# ESP8266_Relay.net
KiCad netlist of a schematic drawn in EAGLE
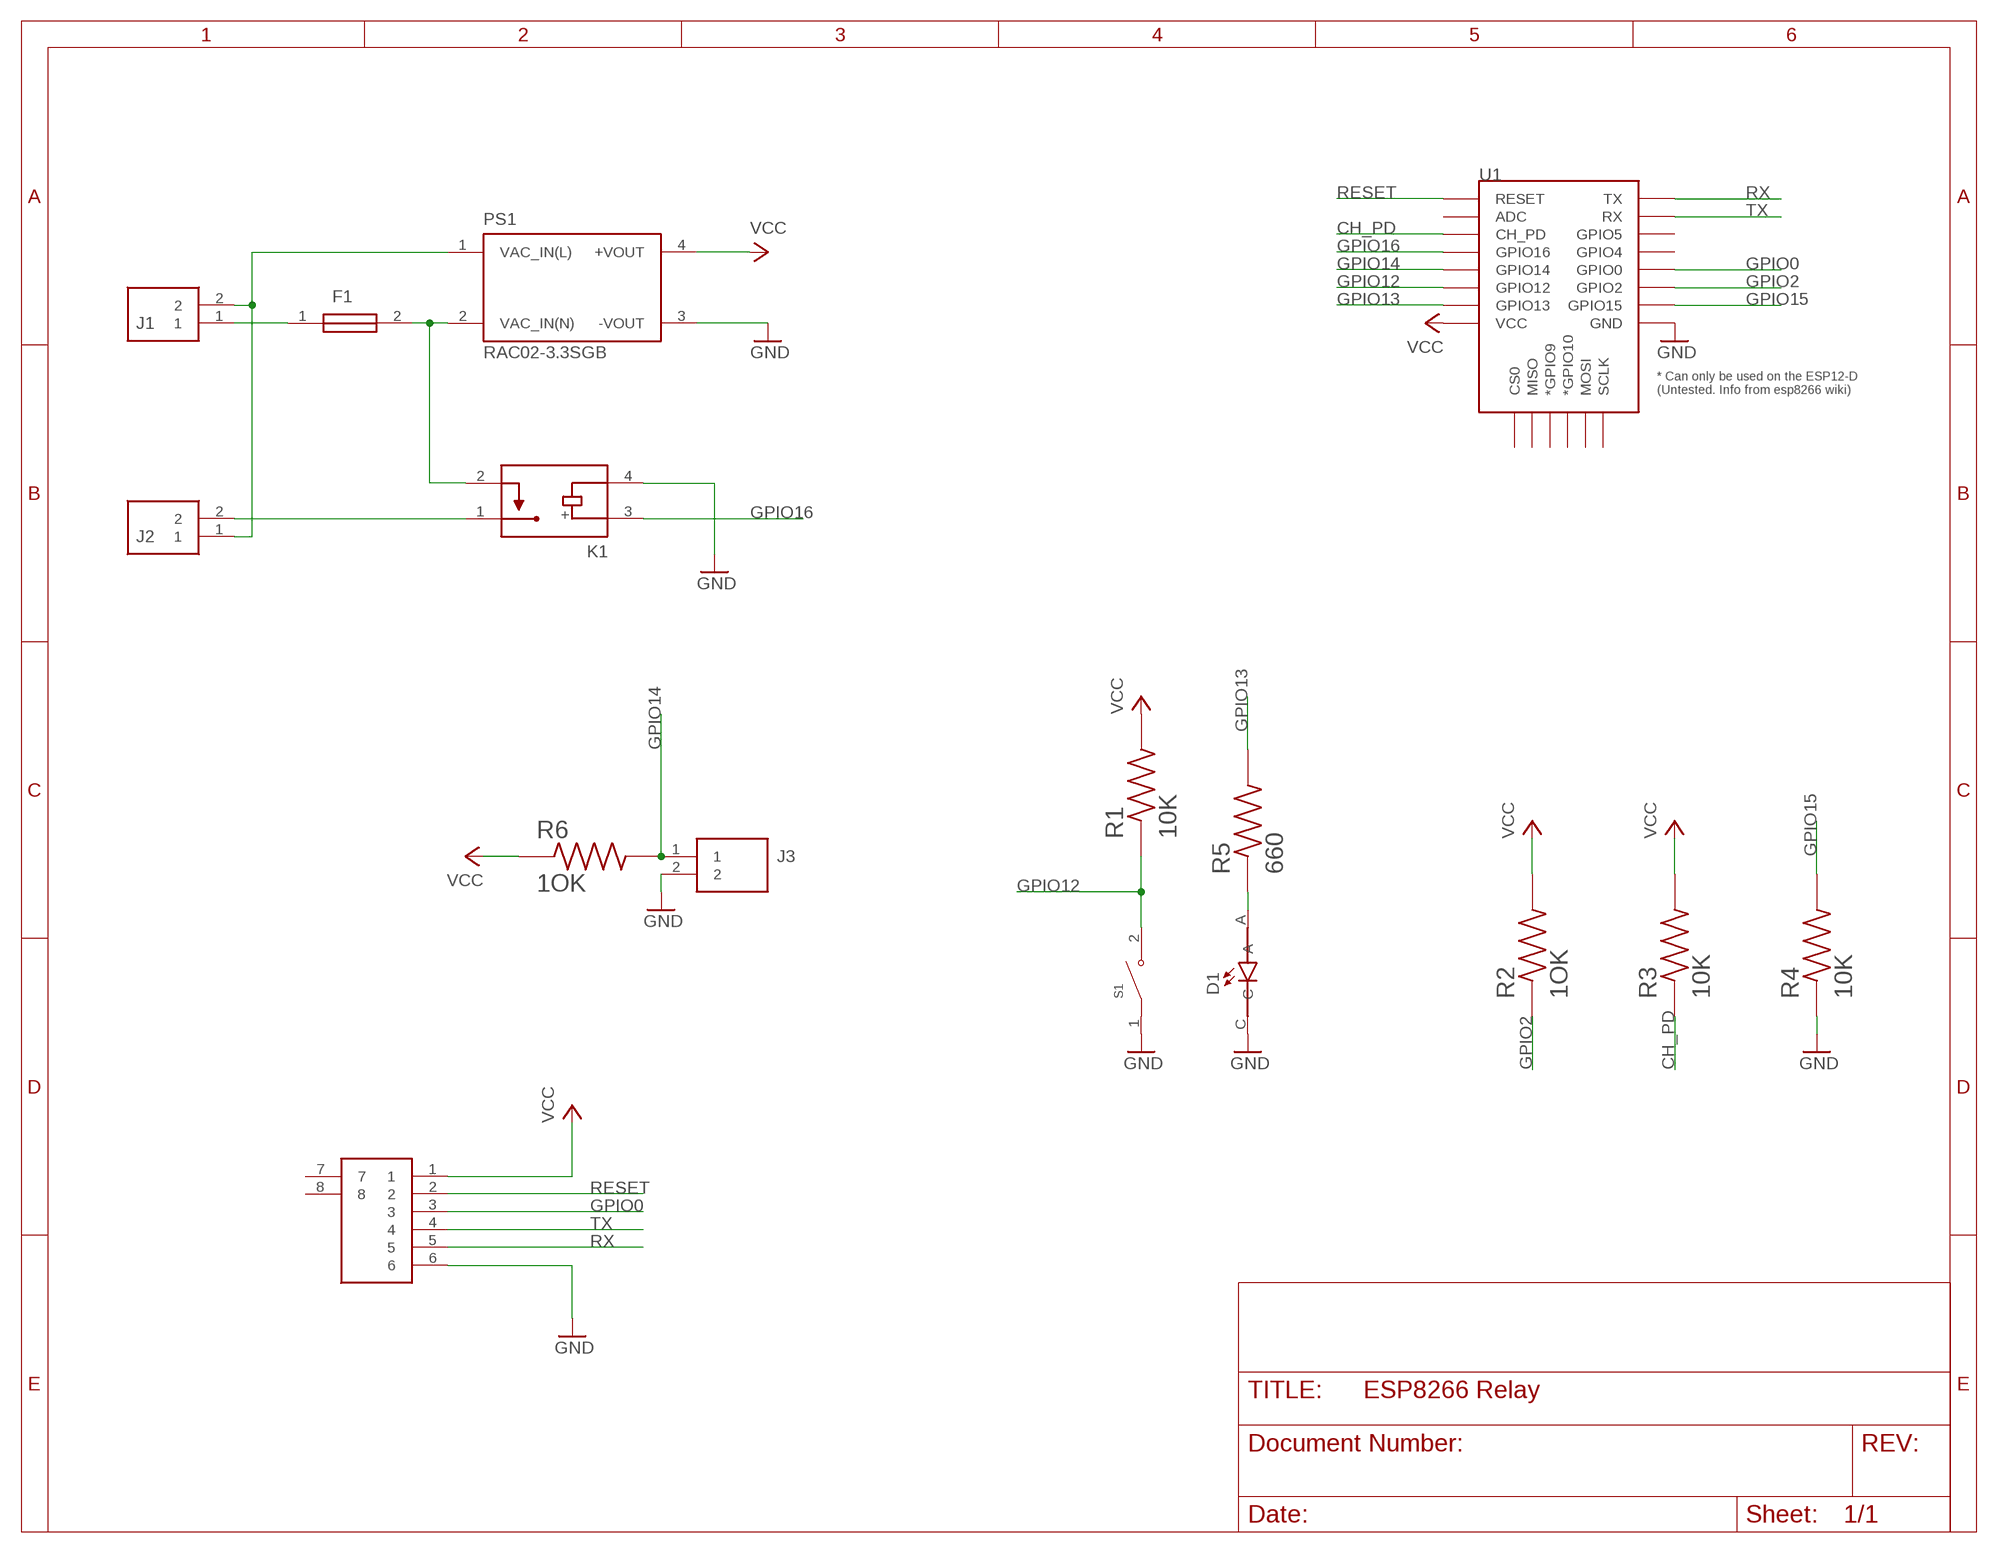
[diagram p0: schematic, sheet 1]

(export (version "E")
  (design (tool "Eeschema 10.0.6"))
  (components
    (comp (ref "D1")
      (value "SML-LXT0805IW-TR")
      (footprint "eagle-import:LEDC2012X120N")
      (fields (field (name "MF") "Lumex Opto/Components"))
      (libsource (lib "eagle-import") (part "SML-LXT0805IW-TR"))
    )
    (comp (ref "F1")
      (value "3404.2469.22")
      (footprint "eagle-import:3404246922")
      (fields (field (name "MOUSER_PART_NUMBER") "693-3404.2469.22"))
      (libsource (lib "eagle-import") (part "3404.2469.22"))
    )
    (comp (ref "J1")
      (value "TB006-508-02BE")
      (footprint "eagle-import:TB00650802BE")
      (fields (field (name "MOUSER_PART_NUMBER") "490-TB006-508-02BE"))
      (libsource (lib "eagle-import") (part "TB006-508-02BE"))
    )
    (comp (ref "J2")
      (value "TB006-508-02BE")
      (footprint "eagle-import:TB00650802BE")
      (fields (field (name "MOUSER_PART_NUMBER") "490-TB006-508-02BE"))
      (libsource (lib "eagle-import") (part "TB006-508-02BE"))
    )
    (comp (ref "J3")
      (value "TB006-508-02BE")
      (footprint "eagle-import:TB00650802BE")
      (fields (field (name "MOUSER_PART_NUMBER") "490-TB006-508-02BE"))
      (libsource (lib "eagle-import") (part "TB006-508-02BE"))
    )
    (comp (ref "J4")
      (value "52852-0670")
      (footprint "eagle-import:528520670")
      (fields (field (name "MOUSER_PART_NUMBER") "538-52852-0670"))
      (libsource (lib "eagle-import") (part "52852-0670"))
    )
    (comp (ref "K1")
      (value "G3MB-202PDC5")
      (footprint "eagle-import:RELAY_G3MB-202PDC5")
      (fields (field (name "MF") "Omron Automation") (field (name "MP") "G3MB-202P DC5"))
      (libsource (lib "eagle-import") (part "G3MB-202PDC5"))
    )
    (comp (ref "PS1")
      (value "RAC02-3.3SGB")
      (footprint "eagle-import:CONV_RAC02-3.3SGB")
      (fields (field (name "MF") "Recom Power"))
      (libsource (lib "eagle-import") (part "RAC02-3.3SGB"))
    )
    (comp (ref "R1")
      (value "10K")
      (footprint "eagle-import:RESC2012X60N")
      (fields (field (name "MF") "Yageo") (field (name "MP") "RC0805FR-07330RL"))
      (libsource (lib "eagle-import") (part "RC0805FR-07330RL"))
    )
    (comp (ref "R2")
      (value "1OK")
      (footprint "eagle-import:RESC2012X60N")
      (fields (field (name "MF") "Yageo") (field (name "MP") "RC0805FR-07330RL"))
      (libsource (lib "eagle-import") (part "RC0805FR-07330RL"))
    )
    (comp (ref "R3")
      (value "10K")
      (footprint "eagle-import:RESC2012X60N")
      (fields (field (name "MF") "Yageo") (field (name "MP") "RC0805FR-07330RL"))
      (libsource (lib "eagle-import") (part "RC0805FR-07330RL"))
    )
    (comp (ref "R4")
      (value "10K")
      (footprint "eagle-import:RESC2012X60N")
      (fields (field (name "MF") "Yageo") (field (name "MP") "RC0805FR-07330RL"))
      (libsource (lib "eagle-import") (part "RC0805FR-07330RL"))
    )
    (comp (ref "R5")
      (value "660")
      (footprint "eagle-import:RESC2012X60N")
      (fields (field (name "MF") "Yageo") (field (name "MP") "RC0805FR-07330RL"))
      (libsource (lib "eagle-import") (part "RC0805FR-07330RL"))
    )
    (comp (ref "R6")
      (value "1OK")
      (footprint "eagle-import:RESC2012X60N")
      (fields (field (name "MF") "Yageo") (field (name "MP") "RC0805FR-07330RL"))
      (libsource (lib "eagle-import") (part "RC0805FR-07330RL"))
    )
    (comp (ref "S1")
      (value "PTS636_SM43J_SMTR_LFS")
      (footprint "eagle-import:SW_PTS636_SM43J_SMTR_LFS")
      (fields (field (name "MF") "C&K") (field (name "MP") "PTS636 SM43J SMTR LFS"))
      (libsource (lib "eagle-import") (part "PTS636_SM43J_SMTR_LFS"))
    )
    (comp (ref "U1")
      (value "ESP12ESMD")
      (footprint "eagle-import:ESP12E-SMD")
      (libsource (lib "eagle-import") (part "ESP12ESMD"))
    )
  )
  (nets
    (net (code "1") (name "/CH_PD") (class "Default")
      (node (ref "R3") (pin "1") (pinfunction "1_1") (pintype "passive"))
      (node (ref "U1") (pin "CH_PD") (pinfunction "CH_PD_CH_PD") (pintype "bidirectional"))
    )
    (net (code "2") (name "/GPIO0") (class "Default")
      (node (ref "J4") (pin "3") (pinfunction "3_3") (pintype "bidirectional"))
      (node (ref "U1") (pin "GPIO0") (pinfunction "GPIO0_GPIO0") (pintype "bidirectional"))
    )
    (net (code "3") (name "/GPIO2") (class "Default")
      (node (ref "R2") (pin "1") (pinfunction "1_1") (pintype "passive"))
      (node (ref "U1") (pin "GPIO2") (pinfunction "GPIO2_GPIO2") (pintype "bidirectional"))
    )
    (net (code "4") (name "/GPIO12") (class "Default")
      (node (ref "R1") (pin "1") (pinfunction "1_1") (pintype "passive"))
      (node (ref "S1") (pin "2") (pinfunction "NO_2") (pintype "passive"))
      (node (ref "U1") (pin "GPIO12") (pinfunction "GPIO12_GPIO12") (pintype "bidirectional"))
    )
    (net (code "5") (name "/GPIO13") (class "Default")
      (node (ref "R5") (pin "2") (pinfunction "2_2") (pintype "passive"))
      (node (ref "U1") (pin "GPIO13") (pinfunction "GPIO13_GPIO13") (pintype "bidirectional"))
    )
    (net (code "6") (name "/GPIO14") (class "Default")
      (node (ref "J3") (pin "1") (pinfunction "1_1") (pintype "bidirectional"))
      (node (ref "R6") (pin "2") (pinfunction "2_2") (pintype "passive"))
      (node (ref "U1") (pin "GPIO14") (pinfunction "GPIO14_GPIO14") (pintype "bidirectional"))
    )
    (net (code "7") (name "/GPIO15") (class "Default")
      (node (ref "R4") (pin "2") (pinfunction "2_2") (pintype "passive"))
      (node (ref "U1") (pin "GPIO15") (pinfunction "GPIO15_GPIO15") (pintype "bidirectional"))
    )
    (net (code "8") (name "/GPIO16") (class "Default")
      (node (ref "K1") (pin "3") (pinfunction "3_3") (pintype "passive"))
      (node (ref "U1") (pin "GPIO16") (pinfunction "GPIO16_GPIO16") (pintype "bidirectional"))
    )
    (net (code "9") (name "/RESET") (class "Default")
      (node (ref "J4") (pin "2") (pinfunction "2_2") (pintype "bidirectional"))
      (node (ref "U1") (pin "RESET") (pinfunction "RESET_RESET") (pintype "bidirectional"))
    )
    (net (code "10") (name "/RX") (class "Default")
      (node (ref "J4") (pin "5") (pinfunction "5_5") (pintype "bidirectional"))
      (node (ref "U1") (pin "TXD0") (pinfunction "TX_TXD0") (pintype "bidirectional"))
    )
    (net (code "11") (name "/TX") (class "Default")
      (node (ref "J4") (pin "4") (pinfunction "4_4") (pintype "bidirectional"))
      (node (ref "U1") (pin "RXD0") (pinfunction "RX_RXD0") (pintype "bidirectional"))
    )
    (net (code "12") (name "GND") (class "Default")
      (node (ref "D1") (pin "C") (pinfunction "C_C") (pintype "passive"))
      (node (ref "J3") (pin "2") (pinfunction "2_2") (pintype "bidirectional"))
      (node (ref "J4") (pin "6") (pinfunction "6_6") (pintype "bidirectional"))
      (node (ref "K1") (pin "4") (pinfunction "4_4") (pintype "passive"))
      (node (ref "PS1") (pin "3") (pinfunction "-VOUT_3") (pintype "output"))
      (node (ref "R4") (pin "1") (pinfunction "1_1") (pintype "passive"))
      (node (ref "S1") (pin "1") (pinfunction "COM_1") (pintype "passive"))
      (node (ref "U1") (pin "GND") (pinfunction "GND_GND") (pintype "bidirectional"))
    )
    (net (code "13") (name "Net-(D1-PadA)") (class "Default")
      (node (ref "D1") (pin "A") (pinfunction "A_A") (pintype "passive"))
      (node (ref "R5") (pin "1") (pinfunction "1_1") (pintype "passive"))
    )
    (net (code "14") (name "Net-(F1-Pad1)") (class "Default")
      (node (ref "F1") (pin "1") (pinfunction "1_1") (pintype "bidirectional"))
      (node (ref "J1") (pin "1") (pinfunction "1_1") (pintype "bidirectional"))
    )
    (net (code "15") (name "Net-(J2-Pad2)") (class "Default")
      (node (ref "J2") (pin "2") (pinfunction "2_2") (pintype "bidirectional"))
      (node (ref "K1") (pin "1") (pinfunction "1_1") (pintype "passive"))
    )
    (net (code "16") (name "Net-(PS1-VAC_IN(L))") (class "Default")
      (node (ref "J1") (pin "2") (pinfunction "2_2") (pintype "bidirectional"))
      (node (ref "J2") (pin "1") (pinfunction "1_1") (pintype "bidirectional"))
      (node (ref "PS1") (pin "1") (pinfunction "VAC_IN(L)_1") (pintype "input"))
    )
    (net (code "17") (name "Net-(PS1-VAC_IN(N))") (class "Default")
      (node (ref "F1") (pin "2") (pinfunction "2_2") (pintype "bidirectional"))
      (node (ref "K1") (pin "2") (pinfunction "2_2") (pintype "passive"))
      (node (ref "PS1") (pin "2") (pinfunction "VAC_IN(N)_2") (pintype "input"))
    )
    (net (code "18") (name "VCC") (class "Default")
      (node (ref "J4") (pin "1") (pinfunction "1_1") (pintype "bidirectional"))
      (node (ref "PS1") (pin "4") (pinfunction "+VOUT_4") (pintype "output"))
      (node (ref "R1") (pin "2") (pinfunction "2_2") (pintype "passive"))
      (node (ref "R2") (pin "2") (pinfunction "2_2") (pintype "passive"))
      (node (ref "R3") (pin "2") (pinfunction "2_2") (pintype "passive"))
      (node (ref "R6") (pin "1") (pinfunction "1_1") (pintype "passive"))
      (node (ref "U1") (pin "VCC") (pinfunction "VCC_VCC") (pintype "bidirectional"))
    )
    (net (code "19") (name "unconnected-(J4-Pad7)") (class "Default")
      (node (ref "J4") (pin "7") (pinfunction "7_7") (pintype "bidirectional"))
    )
    (net (code "20") (name "unconnected-(J4-Pad8)") (class "Default")
      (node (ref "J4") (pin "8") (pinfunction "8_8") (pintype "bidirectional"))
    )
    (net (code "21") (name "unconnected-(U1-*GPIO9-PadGPIO9)") (class "Default")
      (node (ref "U1") (pin "GPIO9") (pinfunction "*GPIO9_GPIO9") (pintype "bidirectional"))
    )
    (net (code "22") (name "unconnected-(U1-*GPIO10-PadGPIO10)") (class "Default")
      (node (ref "U1") (pin "GPIO10") (pinfunction "*GPIO10_GPIO10") (pintype "bidirectional"))
    )
    (net (code "23") (name "unconnected-(U1-PadADC)") (class "Default")
      (node (ref "U1") (pin "ADC") (pinfunction "ADC_ADC") (pintype "bidirectional"))
    )
    (net (code "24") (name "unconnected-(U1-PadCS0)") (class "Default")
      (node (ref "U1") (pin "CS0") (pinfunction "CS0_CS0") (pintype "bidirectional"))
    )
    (net (code "25") (name "unconnected-(U1-PadGPIO4)") (class "Default")
      (node (ref "U1") (pin "GPIO4") (pinfunction "GPIO4_GPIO4") (pintype "bidirectional"))
    )
    (net (code "26") (name "unconnected-(U1-PadGPIO5)") (class "Default")
      (node (ref "U1") (pin "GPIO5") (pinfunction "GPIO5_GPIO5") (pintype "bidirectional"))
    )
    (net (code "27") (name "unconnected-(U1-PadMISO)") (class "Default")
      (node (ref "U1") (pin "MISO") (pinfunction "MISO_MISO") (pintype "bidirectional"))
    )
    (net (code "28") (name "unconnected-(U1-PadMOSI)") (class "Default")
      (node (ref "U1") (pin "MOSI") (pinfunction "MOSI_MOSI") (pintype "bidirectional"))
    )
    (net (code "29") (name "unconnected-(U1-PadSCLK)") (class "Default")
      (node (ref "U1") (pin "SCLK") (pinfunction "SCLK_SCLK") (pintype "bidirectional"))
    )
  )
)
